# MPU_12x12.net
KiCad netlist of a schematic drawn in Altium Designer
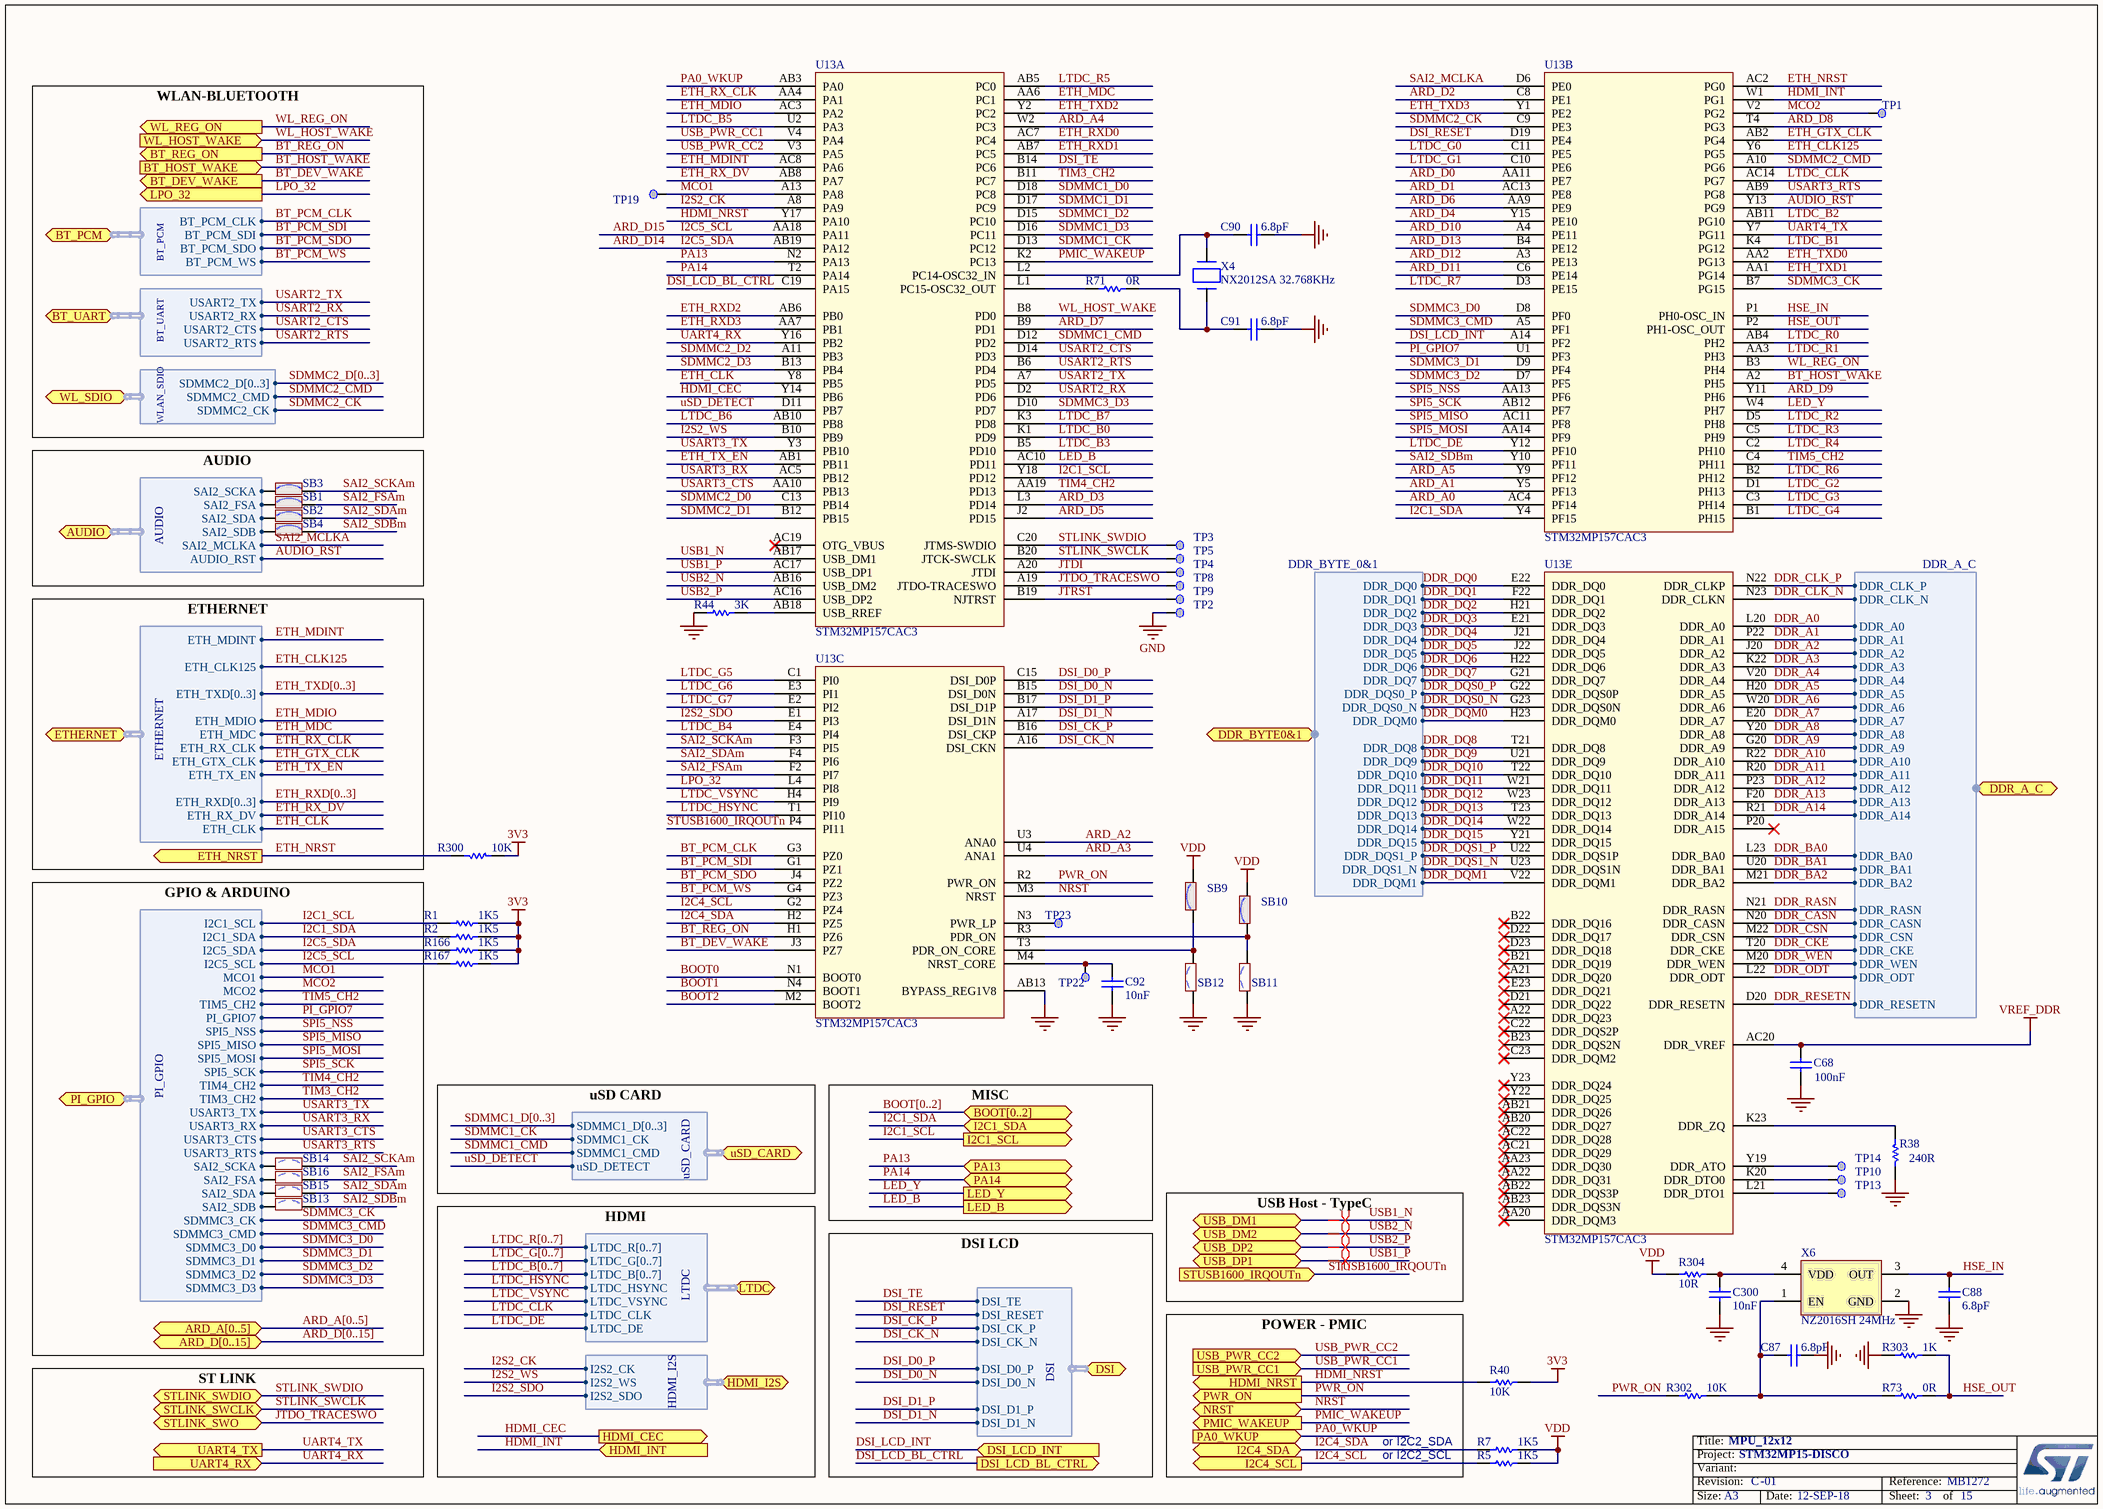
[diagram p0: MPU_12x12.SchDoc]

(export (version "E")
  (design (tool "Eeschema 10.0.6"))
  (components
    (comp (ref "C68")
      (value "100nF")
      (footprint "C0402")
      (description "Capacitor,100nF,16V,X7R,10%,0402")
      (fields
        (field (name "INTERNAL_PART_NUMBER") "MCD-00006")
        (field (name "MANUFACTURER_PART_NUMBER") "CC0402KRX7R7BB104")
        (field (name "PROVIDED_BY") "SUBCO")
      )
      (libsource (lib "MCD_PARTS_database") (part "Capacitor"))
    )
    (comp (ref "C87")
      (value "6.8pF")
      (footprint "C0402")
      (description "Capacitor, MLCC, 6.8pF, 50V, NPO, +-0.25pF, 0402, T=0.5mm")
      (fields
        (field (name "INTERNAL_PART_NUMBER") "MCD-00674")
        (field (name "MANUFACTURER_PART_NUMBER") "CC0402CRNPO9BN6R8")
        (field (name "PROVIDED_BY") "SUBCO")
      )
      (libsource (lib "MCD_PARTS_database") (part "Capacitor"))
    )
    (comp (ref "C88")
      (value "6.8pF")
      (footprint "C0402")
      (description "Capacitor, MLCC, 6.8pF, 50V, NPO, +-0.25pF, 0402, T=0.5mm")
      (fields
        (field (name "INTERNAL_PART_NUMBER") "MCD-00674")
        (field (name "MANUFACTURER_PART_NUMBER") "CC0402CRNPO9BN6R8")
        (field (name "PROVIDED_BY") "SUBCO")
      )
      (libsource (lib "MCD_PARTS_database") (part "Capacitor"))
    )
    (comp (ref "C90")
      (value "6.8pF")
      (footprint "C0402")
      (description "Capacitor, MLCC, 6.8pF, 50V, NPO, +-0.25pF, 0402, T=0.5mm")
      (fields
        (field (name "INTERNAL_PART_NUMBER") "MCD-00674")
        (field (name "MANUFACTURER_PART_NUMBER") "CC0402CRNPO9BN6R8")
        (field (name "PROVIDED_BY") "SUBCO")
      )
      (libsource (lib "MCD_PARTS_database") (part "Capacitor"))
    )
    (comp (ref "C91")
      (value "6.8pF")
      (footprint "C0402")
      (description "Capacitor, MLCC, 6.8pF, 50V, NPO, +-0.25pF, 0402, T=0.5mm")
      (fields
        (field (name "INTERNAL_PART_NUMBER") "MCD-00674")
        (field (name "MANUFACTURER_PART_NUMBER") "CC0402CRNPO9BN6R8")
        (field (name "PROVIDED_BY") "SUBCO")
      )
      (libsource (lib "MCD_PARTS_database") (part "Capacitor"))
    )
    (comp (ref "C92")
      (value "10nF")
      (footprint "C0402")
      (description "Capacitor, MLCC, 10nF, 16V, X7R, 10%, 0402, T=0.5mm")
      (fields
        (field (name "INTERNAL_PART_NUMBER") "MCD-00011")
        (field (name "MANUFACTURER_PART_NUMBER") "CC0402KRX7R7BB103")
        (field (name "PROVIDED_BY") "SUBCO")
      )
      (libsource (lib "MCD_PARTS_database") (part "Capacitor"))
    )
    (comp (ref "C300")
      (value "10nF")
      (footprint "C0402")
      (description "Capacitor, MLCC, 10nF, 16V, X7R, 10%, 0402, T=0.5mm")
      (fields
        (field (name "INTERNAL_PART_NUMBER") "MCD-00011")
        (field (name "MANUFACTURER_PART_NUMBER") "CC0402KRX7R7BB103")
        (field (name "PROVIDED_BY") "SUBCO")
      )
      (libsource (lib "MCD_PARTS_database") (part "Capacitor"))
    )
    (comp (ref "R1")
      (value "1K5")
      (footprint "R0402")
      (description "Resistor,1K5,0402,1%,1/16W")
      (fields
        (field (name "INTERNAL_PART_NUMBER") "MCD-00068")
        (field (name "MANUFACTURER_PART_NUMBER") "RC0402FR-071K5L")
        (field (name "PROVIDED_BY") "SUBCO")
      )
      (libsource (lib "MCD_PARTS_database") (part "Resistor"))
    )
    (comp (ref "R2")
      (value "1K5")
      (footprint "R0402")
      (description "Resistor,1K5,0402,1%,1/16W")
      (fields
        (field (name "INTERNAL_PART_NUMBER") "MCD-00068")
        (field (name "MANUFACTURER_PART_NUMBER") "RC0402FR-071K5L")
        (field (name "PROVIDED_BY") "SUBCO")
      )
      (libsource (lib "MCD_PARTS_database") (part "Resistor"))
    )
    (comp (ref "R5")
      (value "1K5")
      (footprint "R0402")
      (description "Resistor,1K5,0402,1%,1/16W")
      (fields
        (field (name "INTERNAL_PART_NUMBER") "MCD-00068")
        (field (name "MANUFACTURER_PART_NUMBER") "RC0402FR-071K5L")
        (field (name "PROVIDED_BY") "SUBCO")
      )
      (libsource (lib "MCD_PARTS_database") (part "Resistor"))
    )
    (comp (ref "R7")
      (value "1K5")
      (footprint "R0402")
      (description "Resistor,1K5,0402,1%,1/16W")
      (fields
        (field (name "INTERNAL_PART_NUMBER") "MCD-00068")
        (field (name "MANUFACTURER_PART_NUMBER") "RC0402FR-071K5L")
        (field (name "PROVIDED_BY") "SUBCO")
      )
      (libsource (lib "MCD_PARTS_database") (part "Resistor"))
    )
    (comp (ref "R38")
      (value "240R")
      (footprint "R0402")
      (description "Resistor,240R,0402,1%,1/16W")
      (fields
        (field (name "INTERNAL_PART_NUMBER") "MCD-00120")
        (field (name "MANUFACTURER_PART_NUMBER") "RC0402FR-07240RL")
        (field (name "PROVIDED_BY") "SUBCO")
      )
      (libsource (lib "MCD_PARTS_database") (part "Resistor"))
    )
    (comp (ref "R40")
      (value "10K")
      (footprint "R0402")
      (description "Resistor,10K,0402,1%,1/16W")
      (fields
        (field (name "INTERNAL_PART_NUMBER") "MCD-00053")
        (field (name "MANUFACTURER_PART_NUMBER") "RC0402FR-0710KL")
        (field (name "PROVIDED_BY") "SUBCO")
      )
      (libsource (lib "MCD_PARTS_database") (part "Resistor"))
    )
    (comp (ref "R44")
      (value "3K")
      (footprint "R0402")
      (description "Resistor,3K,0402,1%,1/16W")
      (fields
        (field (name "INTERNAL_PART_NUMBER") "MCD-00185")
        (field (name "MANUFACTURER_PART_NUMBER") "RC0402FR-073KL")
        (field (name "PROVIDED_BY") "SUBCO")
      )
      (libsource (lib "MCD_PARTS_database") (part "Resistor"))
    )
    (comp (ref "R71")
      (value "0R")
      (footprint "R0402")
      (description "Resistor,0R,0402,5%,1/16W")
      (fields
        (field (name "INTERNAL_PART_NUMBER") "MCD-00052")
        (field (name "MANUFACTURER_PART_NUMBER") "RC0402JR-070RL")
        (field (name "PROVIDED_BY") "SUBCO")
      )
      (libsource (lib "MCD_PARTS_database") (part "Resistor"))
    )
    (comp (ref "R73")
      (value "0R")
      (footprint "R0402")
      (description "Resistor,0R,0402,5%,1/16W")
      (fields
        (field (name "INTERNAL_PART_NUMBER") "MCD-00052")
        (field (name "MANUFACTURER_PART_NUMBER") "RC0402JR-070RL")
        (field (name "PROVIDED_BY") "SUBCO")
      )
      (libsource (lib "MCD_PARTS_database") (part "Resistor"))
    )
    (comp (ref "R166")
      (value "1K5")
      (footprint "R0402")
      (description "Resistor,1K5,0402,1%,1/16W")
      (fields
        (field (name "INTERNAL_PART_NUMBER") "MCD-00068")
        (field (name "MANUFACTURER_PART_NUMBER") "RC0402FR-071K5L")
        (field (name "PROVIDED_BY") "SUBCO")
      )
      (libsource (lib "MCD_PARTS_database") (part "Resistor"))
    )
    (comp (ref "R167")
      (value "1K5")
      (footprint "R0402")
      (description "Resistor,1K5,0402,1%,1/16W")
      (fields
        (field (name "INTERNAL_PART_NUMBER") "MCD-00068")
        (field (name "MANUFACTURER_PART_NUMBER") "RC0402FR-071K5L")
        (field (name "PROVIDED_BY") "SUBCO")
      )
      (libsource (lib "MCD_PARTS_database") (part "Resistor"))
    )
    (comp (ref "R300")
      (value "10K")
      (footprint "R0402")
      (description "Resistor,10K,0402,1%,1/16W")
      (fields
        (field (name "INTERNAL_PART_NUMBER") "MCD-00053")
        (field (name "MANUFACTURER_PART_NUMBER") "RC0402FR-0710KL")
        (field (name "PROVIDED_BY") "SUBCO")
      )
      (libsource (lib "MCD_PARTS_database") (part "Resistor"))
    )
    (comp (ref "R302")
      (value "10K")
      (footprint "R0402")
      (description "Resistor,10K,0402,1%,1/16W")
      (fields
        (field (name "INTERNAL_PART_NUMBER") "MCD-00053")
        (field (name "MANUFACTURER_PART_NUMBER") "RC0402FR-0710KL")
        (field (name "PROVIDED_BY") "SUBCO")
      )
      (libsource (lib "MCD_PARTS_database") (part "Resistor"))
    )
    (comp (ref "R303")
      (value "1K")
      (footprint "R0402")
      (description "Resistor,1K,0402,1%,1/16W")
      (fields
        (field (name "INTERNAL_PART_NUMBER") "MCD-00061")
        (field (name "MANUFACTURER_PART_NUMBER") "RC0402FR-071KL")
        (field (name "PROVIDED_BY") "SUBCO")
      )
      (libsource (lib "MCD_PARTS_database") (part "Resistor"))
    )
    (comp (ref "R304")
      (value "10R")
      (footprint "R0402")
      (description "Resistor,10R,0402,1%,1/16W")
      (fields
        (field (name "INTERNAL_PART_NUMBER") "MCD-00358")
        (field (name "MANUFACTURER_PART_NUMBER") "RC0402FR-0710RL")
        (field (name "PROVIDED_BY") "SUBCO")
      )
      (libsource (lib "MCD_PARTS_database") (part "Resistor"))
    )
    (comp (ref "SB1")
      (value "~")
      (footprint "SOLDER-BRIDGE_R0603-0R")
      (description "Solder Bridge ON")
      (fields
        (field (name "INTERNAL_PART_NUMBER") "MCD-00071")
        (field (name "MANUFACTURER") "YAGEO")
        (field (name "PROVIDED_BY") "SUBCO")
      )
      (libsource (lib "MCD_PARTS_database") (part "SB_ON"))
    )
    (comp (ref "SB2")
      (value "~")
      (footprint "SOLDER-BRIDGE_R0603-0R")
      (description "Solder Bridge ON")
      (fields
        (field (name "INTERNAL_PART_NUMBER") "MCD-00071")
        (field (name "MANUFACTURER") "YAGEO")
        (field (name "PROVIDED_BY") "SUBCO")
      )
      (libsource (lib "MCD_PARTS_database") (part "SB_ON"))
    )
    (comp (ref "SB3")
      (value "~")
      (footprint "SOLDER-BRIDGE_R0603-0R")
      (description "Solder Bridge ON")
      (fields
        (field (name "INTERNAL_PART_NUMBER") "MCD-00071")
        (field (name "MANUFACTURER") "YAGEO")
        (field (name "PROVIDED_BY") "SUBCO")
      )
      (libsource (lib "MCD_PARTS_database") (part "SB_ON"))
    )
    (comp (ref "SB4")
      (value "~")
      (footprint "SOLDER-BRIDGE_R0603-0R")
      (description "Solder Bridge ON")
      (fields
        (field (name "INTERNAL_PART_NUMBER") "MCD-00071")
        (field (name "MANUFACTURER") "YAGEO")
        (field (name "PROVIDED_BY") "SUBCO")
      )
      (libsource (lib "MCD_PARTS_database") (part "SB_ON"))
    )
    (comp (ref "SB9")
      (value "~")
      (footprint "SOLDER-BRIDGE_R0603-0R")
      (description "Solder Bridge ON")
      (fields
        (field (name "INTERNAL_PART_NUMBER") "MCD-00071")
        (field (name "MANUFACTURER") "YAGEO")
        (field (name "PROVIDED_BY") "SUBCO")
      )
      (libsource (lib "") (part "SB_ON_1"))
    )
    (comp (ref "SB10")
      (value "~")
      (footprint "SOLDER-BRIDGE_R0603-0R")
      (description "Solder Bridge ON")
      (fields
        (field (name "INTERNAL_PART_NUMBER") "MCD-00071")
        (field (name "MANUFACTURER") "YAGEO")
        (field (name "PROVIDED_BY") "SUBCO")
      )
      (libsource (lib "") (part "SB_ON_1"))
    )
    (comp (ref "SB11")
      (value "~")
      (footprint "SOLDER-BRIDGE_R0603-0R")
      (description "Solder Bridge OFF")
      (fields
        (field (name "INTERNAL_PART_NUMBER") "MCD-00072")
        (field (name "MANUFACTURER") "YAGEO")
        (field (name "PROVIDED_BY") "SUBCO")
      )
      (libsource (lib "") (part "SB_OFF_1"))
    )
    (comp (ref "SB12")
      (value "~")
      (footprint "SOLDER-BRIDGE_R0603-0R")
      (description "Solder Bridge OFF")
      (fields
        (field (name "INTERNAL_PART_NUMBER") "MCD-00072")
        (field (name "MANUFACTURER") "YAGEO")
        (field (name "PROVIDED_BY") "SUBCO")
      )
      (libsource (lib "") (part "SB_OFF_1"))
    )
    (comp (ref "SB13")
      (value "~")
      (footprint "SOLDER-BRIDGE_R0603-0R")
      (description "Solder Bridge OFF")
      (fields
        (field (name "INTERNAL_PART_NUMBER") "MCD-00072")
        (field (name "MANUFACTURER") "YAGEO")
        (field (name "PROVIDED_BY") "SUBCO")
      )
      (libsource (lib "MCD_PARTS_database") (part "SB_OFF"))
    )
    (comp (ref "SB14")
      (value "~")
      (footprint "SOLDER-BRIDGE_R0603-0R")
      (description "Solder Bridge OFF")
      (fields
        (field (name "INTERNAL_PART_NUMBER") "MCD-00072")
        (field (name "MANUFACTURER") "YAGEO")
        (field (name "PROVIDED_BY") "SUBCO")
      )
      (libsource (lib "MCD_PARTS_database") (part "SB_OFF"))
    )
    (comp (ref "SB15")
      (value "~")
      (footprint "SOLDER-BRIDGE_R0603-0R")
      (description "Solder Bridge OFF")
      (fields
        (field (name "INTERNAL_PART_NUMBER") "MCD-00072")
        (field (name "MANUFACTURER") "YAGEO")
        (field (name "PROVIDED_BY") "SUBCO")
      )
      (libsource (lib "MCD_PARTS_database") (part "SB_OFF"))
    )
    (comp (ref "SB16")
      (value "~")
      (footprint "SOLDER-BRIDGE_R0603-0R")
      (description "Solder Bridge OFF")
      (fields
        (field (name "INTERNAL_PART_NUMBER") "MCD-00072")
        (field (name "MANUFACTURER") "YAGEO")
        (field (name "PROVIDED_BY") "SUBCO")
      )
      (libsource (lib "MCD_PARTS_database") (part "SB_OFF"))
    )
    (comp (ref "TP1")
      (value "Test Point")
      (footprint "TP_SMD_1MM")
      (description "Test Point 1mm")
      (fields
        (field (name "INTERNAL_PART_NUMBER") "MCD-00074")
        (field (name "MANUFACTURER_PART_NUMBER") "n/a")
      )
      (libsource (lib "MCD_PARTS_database") (part "Test Point"))
    )
    (comp (ref "TP2")
      (value "Test Point")
      (footprint "TP_SMD_1MM")
      (description "Test Point 1mm")
      (fields
        (field (name "INTERNAL_PART_NUMBER") "MCD-00074")
        (field (name "MANUFACTURER_PART_NUMBER") "n/a")
      )
      (libsource (lib "MCD_PARTS_database") (part "Test Point"))
    )
    (comp (ref "TP3")
      (value "Test Point")
      (footprint "TP_SMD_1MM")
      (description "Test Point 1mm")
      (fields
        (field (name "INTERNAL_PART_NUMBER") "MCD-00074")
        (field (name "MANUFACTURER_PART_NUMBER") "n/a")
      )
      (libsource (lib "MCD_PARTS_database") (part "Test Point"))
    )
    (comp (ref "TP4")
      (value "Test Point")
      (footprint "TP_SMD_1MM")
      (description "Test Point 1mm")
      (fields
        (field (name "INTERNAL_PART_NUMBER") "MCD-00074")
        (field (name "MANUFACTURER_PART_NUMBER") "n/a")
      )
      (libsource (lib "MCD_PARTS_database") (part "Test Point"))
    )
    (comp (ref "TP5")
      (value "Test Point")
      (footprint "TP_SMD_1MM")
      (description "Test Point 1mm")
      (fields
        (field (name "INTERNAL_PART_NUMBER") "MCD-00074")
        (field (name "MANUFACTURER_PART_NUMBER") "n/a")
      )
      (libsource (lib "MCD_PARTS_database") (part "Test Point"))
    )
    (comp (ref "TP8")
      (value "Test Point")
      (footprint "TP_SMD_1MM")
      (description "Test Point 1mm")
      (fields
        (field (name "INTERNAL_PART_NUMBER") "MCD-00074")
        (field (name "MANUFACTURER_PART_NUMBER") "n/a")
      )
      (libsource (lib "MCD_PARTS_database") (part "Test Point"))
    )
    (comp (ref "TP9")
      (value "Test Point")
      (footprint "TP_SMD_1MM")
      (description "Test Point 1mm")
      (fields
        (field (name "INTERNAL_PART_NUMBER") "MCD-00074")
        (field (name "MANUFACTURER_PART_NUMBER") "n/a")
      )
      (libsource (lib "MCD_PARTS_database") (part "Test Point"))
    )
    (comp (ref "TP10")
      (value "~")
      (footprint "TP_SMD_0-6MM")
      (description "Test Point 0.6mm")
      (fields (field (name "INTERNAL_PART_NUMBER") "MCD-00631"))
      (libsource (lib "MCD_PARTS_database") (part "Test Point"))
    )
    (comp (ref "TP13")
      (value "~")
      (footprint "TP_SMD_0-6MM")
      (description "Test Point 0.6mm")
      (fields (field (name "INTERNAL_PART_NUMBER") "MCD-00631"))
      (libsource (lib "MCD_PARTS_database") (part "Test Point"))
    )
    (comp (ref "TP14")
      (value "~")
      (footprint "TP_SMD_0-6MM")
      (description "Test Point 0.6mm")
      (fields (field (name "INTERNAL_PART_NUMBER") "MCD-00631"))
      (libsource (lib "MCD_PARTS_database") (part "Test Point"))
    )
    (comp (ref "TP19")
      (value "Test Point")
      (footprint "TP_SMD_1MM")
      (description "Test Point 1mm")
      (fields
        (field (name "INTERNAL_PART_NUMBER") "MCD-00074")
        (field (name "MANUFACTURER_PART_NUMBER") "n/a")
      )
      (libsource (lib "") (part "Test Point_2"))
    )
    (comp (ref "TP22")
      (value "Test Point")
      (footprint "TP_SMD_1MM")
      (description "Test Point 1mm")
      (fields
        (field (name "INTERNAL_PART_NUMBER") "MCD-00074")
        (field (name "MANUFACTURER_PART_NUMBER") "n/a")
      )
      (libsource (lib "") (part "Test Point_1"))
    )
    (comp (ref "TP23")
      (value "Test Point")
      (footprint "TP_SMD_1MM")
      (description "Test Point 1mm")
      (fields
        (field (name "INTERNAL_PART_NUMBER") "MCD-00074")
        (field (name "MANUFACTURER_PART_NUMBER") "n/a")
      )
      (libsource (lib "MCD_PARTS_database") (part "Test Point"))
    )
    (comp (ref "U13")
      (value "STM32MP157CAC3")
      (footprint "ICC_TFBGA361_12X12_STM32MP157CAC3_P050-065")
      (description "MPU TFBGA12x12 secure boot+crypto")
      (fields
        (field (name "INTERNAL_PART_NUMBER") "MCD-00677")
        (field (name "MANUFACTURER") "STMICROELECTRONICS")
        (field (name "PROVIDED_BY") "SUBCO with ST control")
      )
      (libsource (lib "MCD_PARTS_database") (part "STM32MP157CAC3"))
    )
    (comp (ref "X4")
      (value "NX2012SA 32.768KHz")
      (footprint "CRY_NX2012SA_2P")
      (description "Crystal 32.768kHz, 6pF, -+20PPM, R=80K, SMD")
      (fields
        (field (name "INTERNAL_PART_NUMBER") "MCD-01479")
        (field (name "MANUFACTURER_PART_NUMBER") "NX2012SA 32.768KHz EXS00A-MU00527")
        (field (name "PROVIDED_BY") "SUBCO")
      )
      (libsource (lib "MCD_PARTS_database") (part "XTAL_2_PINS"))
    )
    (comp (ref "X6")
      (value "NZ2016SH 24MHz")
      (footprint "CRY_NZ2016SH_4P")
      (description "Oscillator 24Mhz, +-50ppm, Vcc:3.3V typ (1.62V min), square wave: [0.1Vcc;0.9Vcc], Enable pin")
      (fields
        (field (name "INTERNAL_PART_NUMBER") "MCD-01627")
        (field (name "MANUFACTURER_PART_NUMBER") "NZ2016SH 24MHz END4869F")
        (field (name "PROVIDED_BY") "SUBCO")
      )
      (libsource (lib "MCD_PARTS_database") (part "OSCILLATOR_4_PINS"))
    )
  )
  (nets
    (net (code "13") (name "/ARD_A0") (class "Default")
      (node (ref "U13") (pin "AC4") (pinfunction "PF14_AC4") (pintype "passive"))
    )
    (net (code "14") (name "/ARD_A1") (class "Default")
      (node (ref "U13") (pin "Y5") (pinfunction "PF13_Y5") (pintype "passive"))
    )
    (net (code "15") (name "/ARD_A2") (class "Default")
      (node (ref "U13") (pin "U3") (pinfunction "ANA0_U3") (pintype "passive"))
    )
    (net (code "16") (name "/ARD_A3") (class "Default")
      (node (ref "U13") (pin "U4") (pinfunction "ANA1_U4") (pintype "passive"))
    )
    (net (code "17") (name "/ARD_A4") (class "Default")
      (node (ref "U13") (pin "W2") (pinfunction "PC3_W2") (pintype "passive"))
    )
    (net (code "18") (name "/ARD_A5") (class "Default")
      (node (ref "U13") (pin "Y9") (pinfunction "PF12_Y9") (pintype "passive"))
    )
    (net (code "20") (name "/ARD_D0") (class "Default")
      (node (ref "U13") (pin "AA11") (pinfunction "PE7_AA11") (pintype "passive"))
    )
    (net (code "21") (name "/ARD_D1") (class "Default")
      (node (ref "U13") (pin "AC13") (pinfunction "PE8_AC13") (pintype "passive"))
    )
    (net (code "22") (name "/ARD_D2") (class "Default")
      (node (ref "U13") (pin "C8") (pinfunction "PE1_C8") (pintype "passive"))
    )
    (net (code "23") (name "/ARD_D3") (class "Default")
      (node (ref "U13") (pin "L3") (pinfunction "PD14_L3") (pintype "passive"))
    )
    (net (code "24") (name "/ARD_D4") (class "Default")
      (node (ref "U13") (pin "Y15") (pinfunction "PE10_Y15") (pintype "passive"))
    )
    (net (code "25") (name "/ARD_D5") (class "Default")
      (node (ref "U13") (pin "J2") (pinfunction "PD15_J2") (pintype "passive"))
    )
    (net (code "26") (name "/ARD_D6") (class "Default")
      (node (ref "U13") (pin "AA9") (pinfunction "PE9_AA9") (pintype "passive"))
    )
    (net (code "27") (name "/ARD_D7") (class "Default")
      (node (ref "U13") (pin "B9") (pinfunction "PD1_B9") (pintype "passive"))
    )
    (net (code "28") (name "/ARD_D8") (class "Default")
      (node (ref "U13") (pin "T4") (pinfunction "PG3_T4") (pintype "passive"))
    )
    (net (code "29") (name "/ARD_D9") (class "Default")
      (node (ref "U13") (pin "Y11") (pinfunction "PH6_Y11") (pintype "passive"))
    )
    (net (code "30") (name "/ARD_D10") (class "Default")
      (node (ref "U13") (pin "A4") (pinfunction "PE11_A4") (pintype "passive"))
    )
    (net (code "31") (name "/ARD_D11") (class "Default")
      (node (ref "U13") (pin "C6") (pinfunction "PE14_C6") (pintype "passive"))
    )
    (net (code "32") (name "/ARD_D12") (class "Default")
      (node (ref "U13") (pin "A3") (pinfunction "PE13_A3") (pintype "passive"))
    )
    (net (code "33") (name "/ARD_D13") (class "Default")
      (node (ref "U13") (pin "B4") (pinfunction "PE12_B4") (pintype "passive"))
    )
    (net (code "34") (name "/ARD_D14") (class "Default")
      (node (ref "R166") (pin "2") (pinfunction "2_2") (pintype "passive"))
      (node (ref "U13") (pin "AB19") (pinfunction "PA12_AB19") (pintype "passive"))
    )
    (net (code "35") (name "/ARD_D15") (class "Default")
      (node (ref "R167") (pin "2") (pinfunction "2_2") (pintype "passive"))
      (node (ref "U13") (pin "AA18") (pinfunction "PA11_AA18") (pintype "passive"))
    )
    (net (code "37") (name "/AUDIO_RST") (class "Default")
      (node (ref "U13") (pin "Y13") (pinfunction "PG9_Y13") (pintype "passive"))
    )
    (net (code "38") (name "/BOOT0") (class "Default")
      (node (ref "U13") (pin "N1") (pinfunction "BOOT0_N1") (pintype "passive"))
    )
    (net (code "39") (name "/BOOT1") (class "Default")
      (node (ref "U13") (pin "N4") (pinfunction "BOOT1_N4") (pintype "passive"))
    )
    (net (code "40") (name "/BOOT2") (class "Default")
      (node (ref "U13") (pin "M2") (pinfunction "BOOT2_M2") (pintype "passive"))
    )
    (net (code "42") (name "/BT_DEV_WAKE") (class "Default")
      (node (ref "U13") (pin "J3") (pinfunction "PZ7_J3") (pintype "passive"))
    )
    (net (code "43") (name "/BT_HOST_WAKE") (class "Default")
      (node (ref "U13") (pin "A2") (pinfunction "PH5_A2") (pintype "passive"))
    )
    (net (code "44") (name "/BT_PCM_CLK") (class "Default")
      (node (ref "U13") (pin "G3") (pinfunction "PZ0_G3") (pintype "passive"))
    )
    (net (code "45") (name "/BT_PCM_SDI") (class "Default")
      (node (ref "U13") (pin "G1") (pinfunction "PZ1_G1") (pintype "passive"))
    )
    (net (code "46") (name "/BT_PCM_SDO") (class "Default")
      (node (ref "U13") (pin "J4") (pinfunction "PZ2_J4") (pintype "passive"))
    )
    (net (code "47") (name "/BT_PCM_WS") (class "Default")
      (node (ref "U13") (pin "G4") (pinfunction "PZ3_G4") (pintype "passive"))
    )
    (net (code "48") (name "/BT_REG_ON") (class "Default")
      (node (ref "U13") (pin "H1") (pinfunction "PZ6_H1") (pintype "passive"))
    )
    (net (code "49") (name "/DDR_A0") (class "Default")
      (node (ref "U13") (pin "L20") (pinfunction "DDR_A0_L20") (pintype "passive"))
    )
    (net (code "50") (name "/DDR_A1") (class "Default")
      (node (ref "U13") (pin "P22") (pinfunction "DDR_A1_P22") (pintype "passive"))
    )
    (net (code "51") (name "/DDR_A2") (class "Default")
      (node (ref "U13") (pin "J20") (pinfunction "DDR_A2_J20") (pintype "passive"))
    )
    (net (code "52") (name "/DDR_A3") (class "Default")
      (node (ref "U13") (pin "K22") (pinfunction "DDR_A3_K22") (pintype "passive"))
    )
    (net (code "53") (name "/DDR_A4") (class "Default")
      (node (ref "U13") (pin "V20") (pinfunction "DDR_A4_V20") (pintype "passive"))
    )
    (net (code "54") (name "/DDR_A5") (class "Default")
      (node (ref "U13") (pin "H20") (pinfunction "DDR_A5_H20") (pintype "passive"))
    )
    (net (code "55") (name "/DDR_A6") (class "Default")
      (node (ref "U13") (pin "W20") (pinfunction "DDR_A6_W20") (pintype "passive"))
    )
    (net (code "56") (name "/DDR_A7") (class "Default")
      (node (ref "U13") (pin "E20") (pinfunction "DDR_A7_E20") (pintype "passive"))
    )
    (net (code "57") (name "/DDR_A8") (class "Default")
      (node (ref "U13") (pin "Y20") (pinfunction "DDR_A8_Y20") (pintype "passive"))
    )
    (net (code "58") (name "/DDR_A9") (class "Default")
      (node (ref "U13") (pin "G20") (pinfunction "DDR_A9_G20") (pintype "passive"))
    )
    (net (code "59") (name "/DDR_A10") (class "Default")
      (node (ref "U13") (pin "R22") (pinfunction "DDR_A10_R22") (pintype "passive"))
    )
    (net (code "60") (name "/DDR_A11") (class "Default")
      (node (ref "U13") (pin "R20") (pinfunction "DDR_A11_R20") (pintype "passive"))
    )
    (net (code "61") (name "/DDR_A12") (class "Default")
      (node (ref "U13") (pin "P23") (pinfunction "DDR_A12_P23") (pintype "passive"))
    )
    (net (code "62") (name "/DDR_A13") (class "Default")
      (node (ref "U13") (pin "F20") (pinfunction "DDR_A13_F20") (pintype "passive"))
    )
    (net (code "63") (name "/DDR_A14") (class "Default")
      (node (ref "U13") (pin "R21") (pinfunction "DDR_A14_R21") (pintype "passive"))
    )
    (net (code "64") (name "/DDR_BA0") (class "Default")
      (node (ref "U13") (pin "L23") (pinfunction "DDR_BA0_L23") (pintype "passive"))
    )
    (net (code "65") (name "/DDR_BA1") (class "Default")
      (node (ref "U13") (pin "U20") (pinfunction "DDR_BA1_U20") (pintype "passive"))
    )
    (net (code "66") (name "/DDR_BA2") (class "Default")
      (node (ref "U13") (pin "M21") (pinfunction "DDR_BA2_M21") (pintype "passive"))
    )
    (net (code "67") (name "/DDR_CASN") (class "Default")
      (node (ref "U13") (pin "N20") (pinfunction "DDR_CASN_N20") (pintype "passive"))
    )
    (net (code "68") (name "/DDR_CKE") (class "Default")
      (node (ref "U13") (pin "T20") (pinfunction "DDR_CKE_T20") (pintype "passive"))
    )
    (net (code "69") (name "/DDR_CLK_N") (class "Default")
      (node (ref "U13") (pin "N23") (pinfunction "DDR_CLKN_N23") (pintype "passive"))
    )
    (net (code "70") (name "/DDR_CLK_P") (class "Default")
      (node (ref "U13") (pin "N22") (pinfunction "DDR_CLKP_N22") (pintype "passive"))
    )
    (net (code "71") (name "/DDR_CSN") (class "Default")
      (node (ref "U13") (pin "M22") (pinfunction "DDR_CSN_M22") (pintype "passive"))
    )
    (net (code "72") (name "/DDR_DQ0") (class "Default")
      (node (ref "U13") (pin "E22") (pinfunction "DDR_DQ0_E22") (pintype "passive"))
    )
    (net (code "73") (name "/DDR_DQ1") (class "Default")
      (node (ref "U13") (pin "F22") (pinfunction "DDR_DQ1_F22") (pintype "passive"))
    )
    (net (code "74") (name "/DDR_DQ2") (class "Default")
      (node (ref "U13") (pin "H21") (pinfunction "DDR_DQ2_H21") (pintype "passive"))
    )
    (net (code "75") (name "/DDR_DQ3") (class "Default")
      (node (ref "U13") (pin "E21") (pinfunction "DDR_DQ3_E21") (pintype "passive"))
    )
    (net (code "76") (name "/DDR_DQ4") (class "Default")
      (node (ref "U13") (pin "J21") (pinfunction "DDR_DQ4_J21") (pintype "passive"))
    )
    (net (code "77") (name "/DDR_DQ5") (class "Default")
      (node (ref "U13") (pin "J22") (pinfunction "DDR_DQ5_J22") (pintype "passive"))
    )
    (net (code "78") (name "/DDR_DQ6") (class "Default")
      (node (ref "U13") (pin "H22") (pinfunction "DDR_DQ6_H22") (pintype "passive"))
    )
    (net (code "79") (name "/DDR_DQ7") (class "Default")
      (node (ref "U13") (pin "G21") (pinfunction "DDR_DQ7_G21") (pintype "passive"))
    )
    (net (code "80") (name "/DDR_DQ8") (class "Default")
      (node (ref "U13") (pin "T21") (pinfunction "DDR_DQ8_T21") (pintype "passive"))
    )
    (net (code "81") (name "/DDR_DQ9") (class "Default")
      (node (ref "U13") (pin "U21") (pinfunction "DDR_DQ9_U21") (pintype "passive"))
    )
    (net (code "82") (name "/DDR_DQ10") (class "Default")
      (node (ref "U13") (pin "T22") (pinfunction "DDR_DQ10_T22") (pintype "passive"))
    )
    (net (code "83") (name "/DDR_DQ11") (class "Default")
      (node (ref "U13") (pin "W21") (pinfunction "DDR_DQ11_W21") (pintype "passive"))
    )
    (net (code "84") (name "/DDR_DQ12") (class "Default")
      (node (ref "U13") (pin "W23") (pinfunction "DDR_DQ12_W23") (pintype "passive"))
    )
    (net (code "85") (name "/DDR_DQ13") (class "Default")
      (node (ref "U13") (pin "T23") (pinfunction "DDR_DQ13_T23") (pintype "passive"))
    )
    (net (code "86") (name "/DDR_DQ14") (class "Default")
      (node (ref "U13") (pin "W22") (pinfunction "DDR_DQ14_W22") (pintype "passive"))
    )
    (net (code "87") (name "/DDR_DQ15") (class "Default")
      (node (ref "U13") (pin "Y21") (pinfunction "DDR_DQ15_Y21") (pintype "passive"))
    )
    (net (code "88") (name "/DDR_DQM0") (class "Default")
      (node (ref "U13") (pin "H23") (pinfunction "DDR_DQM0_H23") (pintype "passive"))
    )
    (net (code "89") (name "/DDR_DQM1") (class "Default")
      (node (ref "U13") (pin "V22") (pinfunction "DDR_DQM1_V22") (pintype "passive"))
    )
    (net (code "90") (name "/DDR_DQS0_N") (class "Default")
      (node (ref "U13") (pin "G23") (pinfunction "DDR_DQS0N_G23") (pintype "passive"))
    )
    (net (code "91") (name "/DDR_DQS0_P") (class "Default")
      (node (ref "U13") (pin "G22") (pinfunction "DDR_DQS0P_G22") (pintype "passive"))
    )
    (net (code "92") (name "/DDR_DQS1_N") (class "Default")
      (node (ref "U13") (pin "U23") (pinfunction "DDR_DQS1N_U23") (pintype "passive"))
    )
    (net (code "93") (name "/DDR_DQS1_P") (class "Default")
      (node (ref "U13") (pin "U22") (pinfunction "DDR_DQS1P_U22") (pintype "passive"))
    )
    (net (code "94") (name "/DDR_ODT") (class "Default")
      (node (ref "U13") (pin "L22") (pinfunction "DDR_ODT_L22") (pintype "passive"))
    )
    (net (code "95") (name "/DDR_RASN") (class "Default")
      (node (ref "U13") (pin "N21") (pinfunction "DDR_RASN_N21") (pintype "passive"))
    )
    (net (code "96") (name "/DDR_RESETN") (class "Default")
      (node (ref "U13") (pin "D20") (pinfunction "DDR_RESETN_D20") (pintype "passive"))
    )
    (net (code "97") (name "/DDR_WEN") (class "Default")
      (node (ref "U13") (pin "M20") (pinfunction "DDR_WEN_M20") (pintype "passive"))
    )
    (net (code "98") (name "/DSI_CK_N") (class "Default")
      (node (ref "U13") (pin "A16") (pinfunction "DSI_CKN_A16") (pintype "passive"))
    )
    (net (code "99") (name "/DSI_CK_P") (class "Default")
      (node (ref "U13") (pin "B16") (pinfunction "DSI_CKP_B16") (pintype "passive"))
    )
    (net (code "100") (name "/DSI_D0_N") (class "Default")
      (node (ref "U13") (pin "B15") (pinfunction "DSI_D0N_B15") (pintype "passive"))
    )
    (net (code "101") (name "/DSI_D0_P") (class "Default")
      (node (ref "U13") (pin "C15") (pinfunction "DSI_D0P_C15") (pintype "passive"))
    )
    (net (code "102") (name "/DSI_D1_N") (class "Default")
      (node (ref "U13") (pin "A17") (pinfunction "DSI_D1N_A17") (pintype "passive"))
    )
    (net (code "103") (name "/DSI_D1_P") (class "Default")
      (node (ref "U13") (pin "B17") (pinfunction "DSI_D1P_B17") (pintype "passive"))
    )
    (net (code "104") (name "/DSI_LCD_BL_CTRL") (class "Default")
      (node (ref "U13") (pin "C19") (pinfunction "PA15_C19") (pintype "passive"))
    )
    (net (code "105") (name "/DSI_LCD_INT") (class "Default")
      (node (ref "U13") (pin "A14") (pinfunction "PF2_A14") (pintype "passive"))
    )
    (net (code "106") (name "/DSI_RESET") (class "Default")
      (node (ref "U13") (pin "D19") (pinfunction "PE4_D19") (pintype "passive"))
    )
    (net (code "107") (name "/DSI_TE") (class "Default")
      (node (ref "U13") (pin "B14") (pinfunction "PC6_B14") (pintype "passive"))
    )
    (net (code "109") (name "/ETH_CLK") (class "Default")
      (node (ref "U13") (pin "Y8") (pinfunction "PB5_Y8") (pintype "passive"))
    )
    (net (code "110") (name "/ETH_CLK125") (class "Default")
      (node (ref "U13") (pin "Y6") (pinfunction "PG5_Y6") (pintype "passive"))
    )
    (net (code "111") (name "/ETH_GTX_CLK") (class "Default")
      (node (ref "U13") (pin "AB2") (pinfunction "PG4_AB2") (pintype "passive"))
    )
    (net (code "112") (name "/ETH_MDC") (class "Default")
      (node (ref "U13") (pin "AA6") (pinfunction "PC1_AA6") (pintype "passive"))
    )
    (net (code "113") (name "/ETH_MDINT") (class "Default")
      (node (ref "U13") (pin "AC8") (pinfunction "PA6_AC8") (pintype "passive"))
    )
    (net (code "114") (name "/ETH_MDIO") (class "Default")
      (node (ref "U13") (pin "AC3") (pinfunction "PA2_AC3") (pintype "passive"))
    )
    (net (code "115") (name "/ETH_NRST") (class "Default")
      (node (ref "R300") (pin "2") (pinfunction "2_2") (pintype "passive"))
      (node (ref "U13") (pin "AC2") (pinfunction "PG0_AC2") (pintype "passive"))
    )
    (net (code "116") (name "/ETH_RXD0") (class "Default")
      (node (ref "U13") (pin "AC7") (pinfunction "PC4_AC7") (pintype "passive"))
    )
    (net (code "117") (name "/ETH_RXD1") (class "Default")
      (node (ref "U13") (pin "AB7") (pinfunction "PC5_AB7") (pintype "passive"))
    )
    (net (code "118") (name "/ETH_RXD2") (class "Default")
      (node (ref "U13") (pin "AB6") (pinfunction "PB0_AB6") (pintype "passive"))
    )
    (net (code "119") (name "/ETH_RXD3") (class "Default")
      (node (ref "U13") (pin "AA7") (pinfunction "PB1_AA7") (pintype "passive"))
    )
    (net (code "120") (name "/ETH_RX_CLK") (class "Default")
      (node (ref "U13") (pin "AA4") (pinfunction "PA1_AA4") (pintype "passive"))
    )
    (net (code "121") (name "/ETH_RX_DV") (class "Default")
      (node (ref "U13") (pin "AB8") (pinfunction "PA7_AB8") (pintype "passive"))
    )
    (net (code "122") (name "/ETH_TXD0") (class "Default")
      (node (ref "U13") (pin "AA2") (pinfunction "PG13_AA2") (pintype "passive"))
    )
    (net (code "123") (name "/ETH_TXD1") (class "Default")
      (node (ref "U13") (pin "AA1") (pinfunction "PG14_AA1") (pintype "passive"))
    )
    (net (code "124") (name "/ETH_TXD2") (class "Default")
      (node (ref "U13") (pin "Y2") (pinfunction "PC2_Y2") (pintype "passive"))
    )
    (net (code "125") (name "/ETH_TXD3") (class "Default")
      (node (ref "U13") (pin "Y1") (pinfunction "PE2_Y1") (pintype "passive"))
    )
    (net (code "127") (name "/ETH_TX_EN") (class "Default")
      (node (ref "U13") (pin "AB1") (pinfunction "PB11_AB1") (pintype "passive"))
    )
    (net (code "128") (name "/HDMI_CEC") (class "Default")
      (node (ref "U13") (pin "Y14") (pinfunction "PB6_Y14") (pintype "passive"))
    )
    (net (code "129") (name "/HDMI_INT") (class "Default")
      (node (ref "U13") (pin "W1") (pinfunction "PG1_W1") (pintype "passive"))
    )
    (net (code "130") (name "/HDMI_NRST") (class "Default")
      (node (ref "R40") (pin "2") (pinfunction "2_2") (pintype "passive"))
      (node (ref "U13") (pin "Y17") (pinfunction "PA10_Y17") (pintype "passive"))
    )
    (net (code "131") (name "/HSE_IN") (class "Default")
      (node (ref "C88") (pin "2") (pinfunction "2_2") (pintype "passive"))
      (node (ref "U13") (pin "P1") (pinfunction "PH0-OSC_IN_P1") (pintype "passive"))
      (node (ref "X6") (pin "3") (pinfunction "OUT_3") (pintype "passive"))
    )
    (net (code "132") (name "/HSE_OUT") (class "Default")
      (node (ref "R303") (pin "1") (pinfunction "1_1") (pintype "passive"))
      (node (ref "R73") (pin "2") (pinfunction "2_2") (pintype "passive"))
      (node (ref "U13") (pin "P2") (pinfunction "PH1-OSC_OUT_P2") (pintype "passive"))
    )
    (net (code "133") (name "/I2C1_SCL") (class "Default")
      (node (ref "R1") (pin "2") (pinfunction "2_2") (pintype "passive"))
      (node (ref "U13") (pin "Y18") (pinfunction "PD12_Y18") (pintype "passive"))
    )
    (net (code "134") (name "/I2C1_SDA") (class "Default")
      (node (ref "R2") (pin "2") (pinfunction "2_2") (pintype "passive"))
      (node (ref "U13") (pin "Y4") (pinfunction "PF15_Y4") (pintype "passive"))
    )
    (net (code "135") (name "/I2C4_SCL") (class "Default")
      (node (ref "R5") (pin "2") (pinfunction "2_2") (pintype "passive"))
      (node (ref "U13") (pin "G2") (pinfunction "PZ4_G2") (pintype "passive"))
    )
    (net (code "136") (name "/I2C4_SDA") (class "Default")
      (node (ref "R7") (pin "2") (pinfunction "2_2") (pintype "passive"))
      (node (ref "U13") (pin "H2") (pinfunction "PZ5_H2") (pintype "passive"))
    )
    (net (code "137") (name "/I2S2_CK") (class "Default")
      (node (ref "U13") (pin "A8") (pinfunction "PA9_A8") (pintype "passive"))
    )
    (net (code "138") (name "/I2S2_SDO") (class "Default")
      (node (ref "U13") (pin "E1") (pinfunction "PI3_E1") (pintype "passive"))
    )
    (net (code "139") (name "/I2S2_WS") (class "Default")
      (node (ref "U13") (pin "B10") (pinfunction "PB9_B10") (pintype "passive"))
    )
    (net (code "140") (name "/JTDI") (class "Default")
      (node (ref "TP4") (pin "1") (pinfunction "1_1") (pintype "passive"))
      (node (ref "U13") (pin "A20") (pinfunction "JTDI_A20") (pintype "passive"))
    )
    (net (code "141") (name "/JTDO_TRACESWO") (class "Default")
      (node (ref "TP8") (pin "1") (pinfunction "1_1") (pintype "passive"))
      (node (ref "U13") (pin "A19") (pinfunction "JTDO-TRACESWO_A19") (pintype "passive"))
    )
    (net (code "142") (name "/JTRST") (class "Default")
      (node (ref "TP9") (pin "1") (pinfunction "1_1") (pintype "passive"))
      (node (ref "U13") (pin "B19") (pinfunction "NJTRST_B19") (pintype "passive"))
    )
    (net (code "143") (name "/LED_B") (class "Default")
      (node (ref "U13") (pin "AC10") (pinfunction "PD11_AC10") (pintype "passive"))
    )
    (net (code "144") (name "/LED_Y") (class "Default")
      (node (ref "U13") (pin "W4") (pinfunction "PH7_W4") (pintype "passive"))
    )
    (net (code "145") (name "/LPO_32") (class "Default")
      (node (ref "U13") (pin "L4") (pinfunction "PI8_L4") (pintype "passive"))
    )
    (net (code "146") (name "/LTDC_B0") (class "Default")
      (node (ref "U13") (pin "K1") (pinfunction "PD9_K1") (pintype "passive"))
    )
    (net (code "147") (name "/LTDC_B1") (class "Default")
      (node (ref "U13") (pin "K4") (pinfunction "PG12_K4") (pintype "passive"))
    )
    (net (code "148") (name "/LTDC_B2") (class "Default")
      (node (ref "U13") (pin "AB11") (pinfunction "PG10_AB11") (pintype "passive"))
    )
    (net (code "149") (name "/LTDC_B3") (class "Default")
      (node (ref "U13") (pin "B5") (pinfunction "PD10_B5") (pintype "passive"))
    )
    (net (code "150") (name "/LTDC_B4") (class "Default")
      (node (ref "U13") (pin "E4") (pinfunction "PI4_E4") (pintype "passive"))
    )
    (net (code "151") (name "/LTDC_B5") (class "Default")
      (node (ref "U13") (pin "U2") (pinfunction "PA3_U2") (pintype "passive"))
    )
    (net (code "152") (name "/LTDC_B6") (class "Default")
      (node (ref "U13") (pin "AB10") (pinfunction "PB8_AB10") (pintype "passive"))
    )
    (net (code "153") (name "/LTDC_B7") (class "Default")
      (node (ref "U13") (pin "K3") (pinfunction "PD8_K3") (pintype "passive"))
    )
    (net (code "155") (name "/LTDC_CLK") (class "Default")
      (node (ref "U13") (pin "AC14") (pinfunction "PG7_AC14") (pintype "passive"))
    )
    (net (code "156") (name "/LTDC_DE") (class "Default")
      (node (ref "U13") (pin "Y12") (pinfunction "PF10_Y12") (pintype "passive"))
    )
    (net (code "157") (name "/LTDC_G0") (class "Default")
      (node (ref "U13") (pin "C11") (pinfunction "PE5_C11") (pintype "passive"))
    )
    (net (code "158") (name "/LTDC_G1") (class "Default")
      (node (ref "U13") (pin "C10") (pinfunction "PE6_C10") (pintype "passive"))
    )
    (net (code "159") (name "/LTDC_G2") (class "Default")
      (node (ref "U13") (pin "D1") (pinfunction "PH13_D1") (pintype "passive"))
    )
    (net (code "160") (name "/LTDC_G3") (class "Default")
      (node (ref "U13") (pin "C3") (pinfunction "PH14_C3") (pintype "passive"))
    )
    (net (code "161") (name "/LTDC_G4") (class "Default")
      (node (ref "U13") (pin "B1") (pinfunction "PH15_B1") (pintype "passive"))
    )
    (net (code "162") (name "/LTDC_G5") (class "Default")
      (node (ref "U13") (pin "C1") (pinfunction "PI0_C1") (pintype "passive"))
    )
    (net (code "163") (name "/LTDC_G6") (class "Default")
      (node (ref "U13") (pin "E3") (pinfunction "PI1_E3") (pintype "passive"))
    )
    (net (code "164") (name "/LTDC_G7") (class "Default")
      (node (ref "U13") (pin "E2") (pinfunction "PI2_E2") (pintype "passive"))
    )
    (net (code "166") (name "/LTDC_HSYNC") (class "Default")
      (node (ref "U13") (pin "T1") (pinfunction "PI10_T1") (pintype "passive"))
    )
    (net (code "167") (name "/LTDC_R0") (class "Default")
      (node (ref "U13") (pin "AB4") (pinfunction "PH2_AB4") (pintype "passive"))
    )
    (net (code "168") (name "/LTDC_R1") (class "Default")
      (node (ref "U13") (pin "AA3") (pinfunction "PH3_AA3") (pintype "passive"))
    )
    (net (code "169") (name "/LTDC_R2") (class "Default")
      (node (ref "U13") (pin "D5") (pinfunction "PH8_D5") (pintype "passive"))
    )
    (net (code "170") (name "/LTDC_R3") (class "Default")
      (node (ref "U13") (pin "C5") (pinfunction "PH9_C5") (pintype "passive"))
    )
    (net (code "171") (name "/LTDC_R4") (class "Default")
      (node (ref "U13") (pin "C2") (pinfunction "PH10_C2") (pintype "passive"))
    )
    (net (code "172") (name "/LTDC_R5") (class "Default")
      (node (ref "U13") (pin "AB5") (pinfunction "PC0_AB5") (pintype "passive"))
    )
    (net (code "173") (name "/LTDC_R6") (class "Default")
      (node (ref "U13") (pin "B2") (pinfunction "PH12_B2") (pintype "passive"))
    )
    (net (code "174") (name "/LTDC_R7") (class "Default")
      (node (ref "U13") (pin "D3") (pinfunction "PE15_D3") (pintype "passive"))
    )
    (net (code "176") (name "/LTDC_VSYNC") (class "Default")
      (node (ref "U13") (pin "H4") (pinfunction "PI9_H4") (pintype "passive"))
    )
    (net (code "177") (name "/MCO1") (class "Default")
      (node (ref "TP19") (pin "1") (pinfunction "1_1") (pintype "passive"))
      (node (ref "U13") (pin "A13") (pinfunction "PA8_A13") (pintype "passive"))
    )
    (net (code "178") (name "/MCO2") (class "Default")
      (node (ref "TP1") (pin "1") (pinfunction "1_1") (pintype "passive"))
      (node (ref "U13") (pin "V2") (pinfunction "PG2_V2") (pintype "passive"))
    )
    (net (code "179") (name "/NRST") (class "Default")
      (node (ref "U13") (pin "M3") (pinfunction "NRST_M3") (pintype "passive"))
    )
    (net (code "180") (name "/PA0_WKUP") (class "Default")
      (node (ref "U13") (pin "AB3") (pinfunction "PA0_AB3") (pintype "passive"))
    )
    (net (code "181") (name "/PA13") (class "Default")
      (node (ref "U13") (pin "N2") (pinfunction "PA13_N2") (pintype "passive"))
    )
    (net (code "182") (name "/PA14") (class "Default")
      (node (ref "U13") (pin "T2") (pinfunction "PA14_T2") (pintype "passive"))
    )
    (net (code "183") (name "/PI_GPIO7") (class "Default")
      (node (ref "U13") (pin "U1") (pinfunction "PF3_U1") (pintype "passive"))
    )
    (net (code "184") (name "/PMIC_WAKEUP") (class "Default")
      (node (ref "U13") (pin "K2") (pinfunction "PC13_K2") (pintype "passive"))
    )
    (net (code "185") (name "/PWR_ON") (class "Default")
      (node (ref "R302") (pin "2") (pinfunction "2_2") (pintype "passive"))
      (node (ref "U13") (pin "R2") (pinfunction "PWR_ON_R2") (pintype "passive"))
    )
    (net (code "186") (name "/SAI2_FSAm") (class "Default")
      (node (ref "SB1") (pin "2") (pinfunction "2_2") (pintype "passive"))
      (node (ref "SB16") (pin "2") (pinfunction "2_2") (pintype "passive"))
      (node (ref "U13") (pin "F2") (pinfunction "PI7_F2") (pintype "passive"))
    )
    (net (code "187") (name "/SAI2_MCLKA") (class "Default")
      (node (ref "U13") (pin "D6") (pinfunction "PE0_D6") (pintype "passive"))
    )
    (net (code "188") (name "/SAI2_SCKAm") (class "Default")
      (node (ref "SB14") (pin "2") (pinfunction "2_2") (pintype "passive"))
      (node (ref "SB3") (pin "2") (pinfunction "2_2") (pintype "passive"))
      (node (ref "U13") (pin "F3") (pinfunction "PI5_F3") (pintype "passive"))
    )
    (net (code "189") (name "/SAI2_SDAm") (class "Default")
      (node (ref "SB15") (pin "2") (pinfunction "2_2") (pintype "passive"))
      (node (ref "SB2") (pin "2") (pinfunction "2_2") (pintype "passive"))
      (node (ref "U13") (pin "F4") (pinfunction "PI6_F4") (pintype "passive"))
    )
    (net (code "190") (name "/SAI2_SDBm") (class "Default")
      (node (ref "SB13") (pin "2") (pinfunction "2_2") (pintype "passive"))
      (node (ref "SB4") (pin "2") (pinfunction "2_2") (pintype "passive"))
      (node (ref "U13") (pin "Y10") (pinfunction "PF11_Y10") (pintype "passive"))
    )
    (net (code "191") (name "/SDMMC1_CK") (class "Default")
      (node (ref "U13") (pin "D13") (pinfunction "PC12_D13") (pintype "passive"))
    )
    (net (code "192") (name "/SDMMC1_CMD") (class "Default")
      (node (ref "U13") (pin "D12") (pinfunction "PD2_D12") (pintype "passive"))
    )
    (net (code "193") (name "/SDMMC1_D0") (class "Default")
      (node (ref "U13") (pin "D18") (pinfunction "PC8_D18") (pintype "passive"))
    )
    (net (code "194") (name "/SDMMC1_D1") (class "Default")
      (node (ref "U13") (pin "D17") (pinfunction "PC9_D17") (pintype "passive"))
    )
    (net (code "195") (name "/SDMMC1_D2") (class "Default")
      (node (ref "U13") (pin "D15") (pinfunction "PC10_D15") (pintype "passive"))
    )
    (net (code "196") (name "/SDMMC1_D3") (class "Default")
      (node (ref "U13") (pin "D16") (pinfunction "PC11_D16") (pintype "passive"))
    )
    (net (code "198") (name "/SDMMC2_CK") (class "Default")
      (node (ref "U13") (pin "C9") (pinfunction "PE3_C9") (pintype "passive"))
    )
    (net (code "199") (name "/SDMMC2_CMD") (class "Default")
      (node (ref "U13") (pin "A10") (pinfunction "PG6_A10") (pintype "passive"))
    )
    (net (code "200") (name "/SDMMC2_D0") (class "Default")
      (node (ref "U13") (pin "C13") (pinfunction "PB14_C13") (pintype "passive"))
    )
    (net (code "201") (name "/SDMMC2_D1") (class "Default")
      (node (ref "U13") (pin "B12") (pinfunction "PB15_B12") (pintype "passive"))
    )
    (net (code "202") (name "/SDMMC2_D2") (class "Default")
      (node (ref "U13") (pin "A11") (pinfunction "PB3_A11") (pintype "passive"))
    )
    (net (code "203") (name "/SDMMC2_D3") (class "Default")
      (node (ref "U13") (pin "B13") (pinfunction "PB4_B13") (pintype "passive"))
    )
    (net (code "205") (name "/SDMMC3_CK") (class "Default")
      (node (ref "U13") (pin "B7") (pinfunction "PG15_B7") (pintype "passive"))
    )
    (net (code "206") (name "/SDMMC3_CMD") (class "Default")
      (node (ref "U13") (pin "A5") (pinfunction "PF1_A5") (pintype "passive"))
    )
    (net (code "207") (name "/SDMMC3_D0") (class "Default")
      (node (ref "U13") (pin "D8") (pinfunction "PF0_D8") (pintype "passive"))
    )
    (net (code "208") (name "/SDMMC3_D1") (class "Default")
      (node (ref "U13") (pin "D9") (pinfunction "PF4_D9") (pintype "passive"))
    )
    (net (code "209") (name "/SDMMC3_D2") (class "Default")
      (node (ref "U13") (pin "D7") (pinfunction "PF5_D7") (pintype "passive"))
    )
    (net (code "210") (name "/SDMMC3_D3") (class "Default")
      (node (ref "U13") (pin "D10") (pinfunction "PD7_D10") (pintype "passive"))
    )
    (net (code "211") (name "/SPI5_MISO") (class "Default")
      (node (ref "U13") (pin "AC11") (pinfunction "PF8_AC11") (pintype "passive"))
    )
    (net (code "212") (name "/SPI5_MOSI") (class "Default")
      (node (ref "U13") (pin "AA14") (pinfunction "PF9_AA14") (pintype "passive"))
    )
    (net (code "213") (name "/SPI5_NSS") (class "Default")
      (node (ref "U13") (pin "AA13") (pinfunction "PF6_AA13") (pintype "passive"))
    )
    (net (code "214") (name "/SPI5_SCK") (class "Default")
      (node (ref "U13") (pin "AB12") (pinfunction "PF7_AB12") (pintype "passive"))
    )
    (net (code "215") (name "/STLINK_SWCLK") (class "Default")
      (node (ref "TP5") (pin "1") (pinfunction "1_1") (pintype "passive"))
      (node (ref "U13") (pin "B20") (pinfunction "JTCK-SWCLK_B20") (pintype "passive"))
    )
    (net (code "216") (name "/STLINK_SWDIO") (class "Default")
      (node (ref "TP3") (pin "1") (pinfunction "1_1") (pintype "passive"))
      (node (ref "U13") (pin "C20") (pinfunction "JTMS-SWDIO_C20") (pintype "passive"))
    )
    (net (code "217") (name "/STUSB1600_IRQOUTn") (class "Default")
      (node (ref "U13") (pin "P4") (pinfunction "PI11_P4") (pintype "passive"))
    )
    (net (code "218") (name "/TIM3_CH2") (class "Default")
      (node (ref "U13") (pin "B11") (pinfunction "PC7_B11") (pintype "passive"))
    )
    (net (code "219") (name "/TIM4_CH2") (class "Default")
      (node (ref "U13") (pin "AA19") (pinfunction "PD13_AA19") (pintype "passive"))
    )
    (net (code "220") (name "/TIM5_CH2") (class "Default")
      (node (ref "U13") (pin "C4") (pinfunction "PH11_C4") (pintype "passive"))
    )
    (net (code "221") (name "/UART4_RX") (class "Default")
      (node (ref "U13") (pin "Y16") (pinfunction "PB2_Y16") (pintype "passive"))
    )
    (net (code "222") (name "/UART4_TX") (class "Default")
      (node (ref "U13") (pin "Y7") (pinfunction "PG11_Y7") (pintype "passive"))
    )
    (net (code "223") (name "/USART2_CTS") (class "Default")
      (node (ref "U13") (pin "D14") (pinfunction "PD3_D14") (pintype "passive"))
    )
    (net (code "224") (name "/USART2_RTS") (class "Default")
      (node (ref "U13") (pin "B6") (pinfunction "PD4_B6") (pintype "passive"))
    )
    (net (code "225") (name "/USART2_RX") (class "Default")
      (node (ref "U13") (pin "D2") (pinfunction "PD6_D2") (pintype "passive"))
    )
    (net (code "226") (name "/USART2_TX") (class "Default")
      (node (ref "U13") (pin "A7") (pinfunction "PD5_A7") (pintype "passive"))
    )
    (net (code "227") (name "/USART3_CTS") (class "Default")
      (node (ref "U13") (pin "AA10") (pinfunction "PB13_AA10") (pintype "passive"))
    )
    (net (code "228") (name "/USART3_RTS") (class "Default")
      (node (ref "U13") (pin "AB9") (pinfunction "PG8_AB9") (pintype "passive"))
    )
    (net (code "229") (name "/USART3_RX") (class "Default")
      (node (ref "U13") (pin "AC5") (pinfunction "PB12_AC5") (pintype "passive"))
    )
    (net (code "230") (name "/USART3_TX") (class "Default")
      (node (ref "U13") (pin "Y3") (pinfunction "PB10_Y3") (pintype "passive"))
    )
    (net (code "231") (name "/USB1_N") (class "Default")
      (node (ref "U13") (pin "AB17") (pinfunction "USB_DM1_AB17") (pintype "passive"))
    )
    (net (code "232") (name "/USB1_P") (class "Default")
      (node (ref "U13") (pin "AC17") (pinfunction "USB_DP1_AC17") (pintype "passive"))
    )
    (net (code "233") (name "/USB2_N") (class "Default")
      (node (ref "U13") (pin "AB16") (pinfunction "USB_DM2_AB16") (pintype "passive"))
    )
    (net (code "234") (name "/USB2_P") (class "Default")
      (node (ref "U13") (pin "AC16") (pinfunction "USB_DP2_AC16") (pintype "passive"))
    )
    (net (code "235") (name "/USB_PWR_CC1") (class "Default")
      (node (ref "U13") (pin "V4") (pinfunction "PA4_V4") (pintype "passive"))
    )
    (net (code "236") (name "/USB_PWR_CC2") (class "Default")
      (node (ref "U13") (pin "V3") (pinfunction "PA5_V3") (pintype "passive"))
    )
    (net (code "237") (name "/WL_HOST_WAKE") (class "Default")
      (node (ref "U13") (pin "B8") (pinfunction "PD0_B8") (pintype "passive"))
    )
    (net (code "238") (name "/WL_REG_ON") (class "Default")
      (node (ref "U13") (pin "B3") (pinfunction "PH4_B3") (pintype "passive"))
    )
    (net (code "239") (name "/uSD_DETECT") (class "Default")
      (node (ref "U13") (pin "D11") (pinfunction "PB7_D11") (pintype "passive"))
    )
    (net (code "252") (name "3V3") (class "Default")
      (node (ref "R1") (pin "1") (pinfunction "1_1") (pintype "passive"))
      (node (ref "R166") (pin "1") (pinfunction "1_1") (pintype "passive"))
      (node (ref "R167") (pin "1") (pinfunction "1_1") (pintype "passive"))
      (node (ref "R2") (pin "1") (pinfunction "1_1") (pintype "passive"))
      (node (ref "R300") (pin "1") (pinfunction "1_1") (pintype "passive"))
      (node (ref "R40") (pin "1") (pinfunction "1_1") (pintype "passive"))
    )
    (net (code "253") (name "GND") (class "Default")
      (node (ref "C300") (pin "1") (pinfunction "1_1") (pintype "passive"))
      (node (ref "C68") (pin "1") (pinfunction "1_1") (pintype "passive"))
      (node (ref "C87") (pin "2") (pinfunction "2_2") (pintype "passive"))
      (node (ref "C88") (pin "1") (pinfunction "1_1") (pintype "passive"))
      (node (ref "C90") (pin "2") (pinfunction "2_2") (pintype "passive"))
      (node (ref "C91") (pin "2") (pinfunction "2_2") (pintype "passive"))
      (node (ref "C92") (pin "1") (pinfunction "1_1") (pintype "passive"))
      (node (ref "R303") (pin "2") (pinfunction "2_2") (pintype "passive"))
      (node (ref "R38") (pin "2") (pinfunction "2_2") (pintype "passive"))
      (node (ref "R44") (pin "1") (pinfunction "1_1") (pintype "passive"))
      (node (ref "SB11") (pin "1") (pinfunction "1_1") (pintype "passive"))
      (node (ref "SB12") (pin "1") (pinfunction "1_1") (pintype "passive"))
      (node (ref "TP2") (pin "1") (pinfunction "1_1") (pintype "passive"))
      (node (ref "U13") (pin "AB13") (pinfunction "BYPASS_REG1V8_AB13") (pintype "passive"))
      (node (ref "X6") (pin "2") (pinfunction "GND_2") (pintype "passive"))
    )
    (net (code "254") (name "Net-(U13A-PC14-OSC32_IN)") (class "Default")
      (node (ref "C90") (pin "1") (pinfunction "1_1") (pintype "passive"))
      (node (ref "U13") (pin "L2") (pinfunction "PC14-OSC32_IN_L2") (pintype "passive"))
      (node (ref "X4") (pin "2") (pinfunction "X2_2") (pintype "passive"))
    )
    (net (code "255") (name "Net-(U13A-PC15-OSC32_OUT)") (class "Default")
      (node (ref "R71") (pin "1") (pinfunction "1_1") (pintype "passive"))
      (node (ref "U13") (pin "L1") (pinfunction "PC15-OSC32_OUT_L1") (pintype "passive"))
    )
    (net (code "256") (name "Net-(U13A-USB_RREF)") (class "Default")
      (node (ref "R44") (pin "2") (pinfunction "2_2") (pintype "passive"))
      (node (ref "U13") (pin "AB18") (pinfunction "USB_RREF_AB18") (pintype "passive"))
    )
    (net (code "257") (name "Net-(U13C-NRST_CORE)") (class "Default")
      (node (ref "C92") (pin "2") (pinfunction "2_2") (pintype "passive"))
      (node (ref "TP22") (pin "1") (pinfunction "1_1") (pintype "passive"))
      (node (ref "U13") (pin "M4") (pinfunction "NRST_CORE_M4") (pintype "passive"))
    )
    (net (code "258") (name "Net-(U13C-PDR_ON)") (class "Default")
      (node (ref "SB10") (pin "1") (pinfunction "1_1") (pintype "passive"))
      (node (ref "SB11") (pin "2") (pinfunction "2_2") (pintype "passive"))
      (node (ref "U13") (pin "R3") (pinfunction "PDR_ON_R3") (pintype "passive"))
    )
    (net (code "259") (name "Net-(U13C-PDR_ON_CORE)") (class "Default")
      (node (ref "SB12") (pin "2") (pinfunction "2_2") (pintype "passive"))
      (node (ref "SB9") (pin "1") (pinfunction "1_1") (pintype "passive"))
      (node (ref "U13") (pin "T3") (pinfunction "PDR_ON_CORE_T3") (pintype "passive"))
    )
    (net (code "260") (name "Net-(U13C-PWR_LP)") (class "Default")
      (node (ref "TP23") (pin "1") (pinfunction "1_1") (pintype "passive"))
      (node (ref "U13") (pin "N3") (pinfunction "PWR_LP_N3") (pintype "passive"))
    )
    (net (code "261") (name "Net-(U13E-DDR_ATO)") (class "Default")
      (node (ref "TP14") (pin "1") (pinfunction "1_1") (pintype "passive"))
      (node (ref "U13") (pin "Y19") (pinfunction "DDR_ATO_Y19") (pintype "passive"))
    )
    (net (code "262") (name "Net-(U13E-DDR_DTO0)") (class "Default")
      (node (ref "TP10") (pin "1") (pinfunction "1_1") (pintype "passive"))
      (node (ref "U13") (pin "K20") (pinfunction "DDR_DTO0_K20") (pintype "passive"))
    )
    (net (code "263") (name "Net-(U13E-DDR_DTO1)") (class "Default")
      (node (ref "TP13") (pin "1") (pinfunction "1_1") (pintype "passive"))
      (node (ref "U13") (pin "L21") (pinfunction "DDR_DTO1_L21") (pintype "passive"))
    )
    (net (code "264") (name "Net-(U13E-DDR_ZQ)") (class "Default")
      (node (ref "R38") (pin "1") (pinfunction "1_1") (pintype "passive"))
      (node (ref "U13") (pin "K23") (pinfunction "DDR_ZQ_K23") (pintype "passive"))
    )
    (net (code "265") (name "Net-(X4-X1)") (class "Default")
      (node (ref "C91") (pin "1") (pinfunction "1_1") (pintype "passive"))
      (node (ref "R71") (pin "2") (pinfunction "2_2") (pintype "passive"))
      (node (ref "X4") (pin "1") (pinfunction "X1_1") (pintype "passive"))
    )
    (net (code "266") (name "Net-(X6-EN)") (class "Default")
      (node (ref "C87") (pin "1") (pinfunction "1_1") (pintype "passive"))
      (node (ref "R302") (pin "1") (pinfunction "1_1") (pintype "passive"))
      (node (ref "R73") (pin "1") (pinfunction "1_1") (pintype "passive"))
      (node (ref "X6") (pin "1") (pinfunction "EN_1") (pintype "passive"))
    )
    (net (code "267") (name "Net-(X6-VDD)") (class "Default")
      (node (ref "C300") (pin "2") (pinfunction "2_2") (pintype "passive"))
      (node (ref "R304") (pin "2") (pinfunction "2_2") (pintype "passive"))
      (node (ref "X6") (pin "4") (pinfunction "VDD_4") (pintype "passive"))
    )
    (net (code "268") (name "VDD") (class "Default")
      (node (ref "R304") (pin "1") (pinfunction "1_1") (pintype "passive"))
      (node (ref "R5") (pin "1") (pinfunction "1_1") (pintype "passive"))
      (node (ref "R7") (pin "1") (pinfunction "1_1") (pintype "passive"))
      (node (ref "SB10") (pin "2") (pinfunction "2_2") (pintype "passive"))
      (node (ref "SB9") (pin "2") (pinfunction "2_2") (pintype "passive"))
    )
    (net (code "269") (name "VREF_DDR") (class "Default")
      (node (ref "C68") (pin "2") (pinfunction "2_2") (pintype "passive"))
      (node (ref "U13") (pin "AC20") (pinfunction "DDR_VREF_AC20") (pintype "passive"))
    )
    (net (code "270") (name "unconnected-(SB1-Pad1)") (class "Default")
      (node (ref "SB1") (pin "1") (pinfunction "1_1") (pintype "passive"))
    )
    (net (code "271") (name "unconnected-(SB2-Pad1)") (class "Default")
      (node (ref "SB2") (pin "1") (pinfunction "1_1") (pintype "passive"))
    )
    (net (code "272") (name "unconnected-(SB3-Pad1)") (class "Default")
      (node (ref "SB3") (pin "1") (pinfunction "1_1") (pintype "passive"))
    )
    (net (code "273") (name "unconnected-(SB4-Pad1)") (class "Default")
      (node (ref "SB4") (pin "1") (pinfunction "1_1") (pintype "passive"))
    )
    (net (code "274") (name "unconnected-(SB13-Pad1)") (class "Default")
      (node (ref "SB13") (pin "1") (pinfunction "1_1") (pintype "passive"))
    )
    (net (code "275") (name "unconnected-(SB14-Pad1)") (class "Default")
      (node (ref "SB14") (pin "1") (pinfunction "1_1") (pintype "passive"))
    )
    (net (code "276") (name "unconnected-(SB15-Pad1)") (class "Default")
      (node (ref "SB15") (pin "1") (pinfunction "1_1") (pintype "passive"))
    )
    (net (code "277") (name "unconnected-(SB16-Pad1)") (class "Default")
      (node (ref "SB16") (pin "1") (pinfunction "1_1") (pintype "passive"))
    )
    (net (code "278") (name "unconnected-(U13A-OTG_VBUS-PadAC19)") (class "Default")
      (node (ref "U13") (pin "AC19") (pinfunction "OTG_VBUS_AC19") (pintype "passive+no_connect"))
    )
    (net (code "279") (name "unconnected-(U13E-DDR_A15-PadP20)") (class "Default")
      (node (ref "U13") (pin "P20") (pinfunction "DDR_A15_P20") (pintype "passive+no_connect"))
    )
    (net (code "280") (name "unconnected-(U13E-DDR_DQ16-PadB22)") (class "Default")
      (node (ref "U13") (pin "B22") (pinfunction "DDR_DQ16_B22") (pintype "passive+no_connect"))
    )
    (net (code "281") (name "unconnected-(U13E-DDR_DQ17-PadD22)") (class "Default")
      (node (ref "U13") (pin "D22") (pinfunction "DDR_DQ17_D22") (pintype "passive+no_connect"))
    )
    (net (code "282") (name "unconnected-(U13E-DDR_DQ18-PadD23)") (class "Default")
      (node (ref "U13") (pin "D23") (pinfunction "DDR_DQ18_D23") (pintype "passive+no_connect"))
    )
    (net (code "283") (name "unconnected-(U13E-DDR_DQ19-PadB21)") (class "Default")
      (node (ref "U13") (pin "B21") (pinfunction "DDR_DQ19_B21") (pintype "passive+no_connect"))
    )
    (net (code "284") (name "unconnected-(U13E-DDR_DQ20-PadA21)") (class "Default")
      (node (ref "U13") (pin "A21") (pinfunction "DDR_DQ20_A21") (pintype "passive+no_connect"))
    )
    (net (code "285") (name "unconnected-(U13E-DDR_DQ21-PadE23)") (class "Default")
      (node (ref "U13") (pin "E23") (pinfunction "DDR_DQ21_E23") (pintype "passive+no_connect"))
    )
    (net (code "286") (name "unconnected-(U13E-DDR_DQ22-PadD21)") (class "Default")
      (node (ref "U13") (pin "D21") (pinfunction "DDR_DQ22_D21") (pintype "passive+no_connect"))
    )
    (net (code "287") (name "unconnected-(U13E-DDR_DQ23-PadA22)") (class "Default")
      (node (ref "U13") (pin "A22") (pinfunction "DDR_DQ23_A22") (pintype "passive+no_connect"))
    )
    (net (code "288") (name "unconnected-(U13E-DDR_DQ24-PadY23)") (class "Default")
      (node (ref "U13") (pin "Y23") (pinfunction "DDR_DQ24_Y23") (pintype "passive+no_connect"))
    )
    (net (code "289") (name "unconnected-(U13E-DDR_DQ25-PadY22)") (class "Default")
      (node (ref "U13") (pin "Y22") (pinfunction "DDR_DQ25_Y22") (pintype "passive+no_connect"))
    )
    (net (code "290") (name "unconnected-(U13E-DDR_DQ26-PadAB21)") (class "Default")
      (node (ref "U13") (pin "AB21") (pinfunction "DDR_DQ26_AB21") (pintype "passive+no_connect"))
    )
    (net (code "291") (name "unconnected-(U13E-DDR_DQ27-PadAB20)") (class "Default")
      (node (ref "U13") (pin "AB20") (pinfunction "DDR_DQ27_AB20") (pintype "passive+no_connect"))
    )
    (net (code "292") (name "unconnected-(U13E-DDR_DQ28-PadAC22)") (class "Default")
      (node (ref "U13") (pin "AC22") (pinfunction "DDR_DQ28_AC22") (pintype "passive+no_connect"))
    )
    (net (code "293") (name "unconnected-(U13E-DDR_DQ29-PadAC21)") (class "Default")
      (node (ref "U13") (pin "AC21") (pinfunction "DDR_DQ29_AC21") (pintype "passive+no_connect"))
    )
    (net (code "294") (name "unconnected-(U13E-DDR_DQ30-PadAA23)") (class "Default")
      (node (ref "U13") (pin "AA23") (pinfunction "DDR_DQ30_AA23") (pintype "passive+no_connect"))
    )
    (net (code "295") (name "unconnected-(U13E-DDR_DQ31-PadAA22)") (class "Default")
      (node (ref "U13") (pin "AA22") (pinfunction "DDR_DQ31_AA22") (pintype "passive+no_connect"))
    )
    (net (code "296") (name "unconnected-(U13E-DDR_DQM2-PadC23)") (class "Default")
      (node (ref "U13") (pin "C23") (pinfunction "DDR_DQM2_C23") (pintype "passive+no_connect"))
    )
    (net (code "297") (name "unconnected-(U13E-DDR_DQM3-PadAA20)") (class "Default")
      (node (ref "U13") (pin "AA20") (pinfunction "DDR_DQM3_AA20") (pintype "passive+no_connect"))
    )
    (net (code "298") (name "unconnected-(U13E-DDR_DQS2N-PadB23)") (class "Default")
      (node (ref "U13") (pin "B23") (pinfunction "DDR_DQS2N_B23") (pintype "passive+no_connect"))
    )
    (net (code "299") (name "unconnected-(U13E-DDR_DQS2P-PadC22)") (class "Default")
      (node (ref "U13") (pin "C22") (pinfunction "DDR_DQS2P_C22") (pintype "passive+no_connect"))
    )
    (net (code "300") (name "unconnected-(U13E-DDR_DQS3N-PadAB23)") (class "Default")
      (node (ref "U13") (pin "AB23") (pinfunction "DDR_DQS3N_AB23") (pintype "passive+no_connect"))
    )
    (net (code "301") (name "unconnected-(U13E-DDR_DQS3P-PadAB22)") (class "Default")
      (node (ref "U13") (pin "AB22") (pinfunction "DDR_DQS3P_AB22") (pintype "passive+no_connect"))
    )
  )
)
